# Fuente.net
KiCad netlist of a schematic drawn in EAGLE
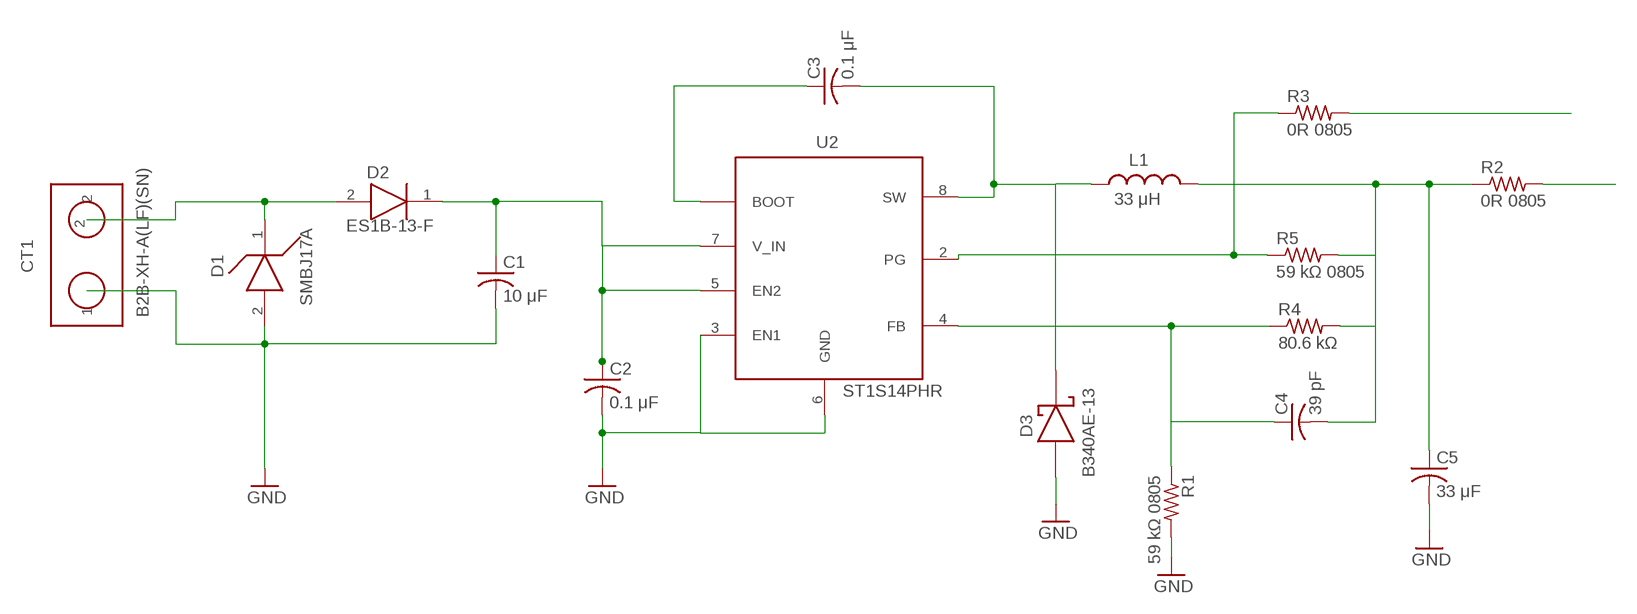
[diagram p0: schematic, sheet 1]

(export (version "E")
  (design (tool "Eeschema 10.0.6"))
  (components
    (comp (ref "C1")
      (value "10 μF")
      (footprint "eagle-import:C0805")
      (fields (field (name "PART_NO") "GRM21BR61H106KE43L"))
      (libsource (lib "eagle-import") (part "C-USC0805"))
    )
    (comp (ref "C2")
      (value "0.1 μF")
      (footprint "eagle-import:C0805")
      (fields (field (name "PART_NO") "GCM21BR72A104KA37L"))
      (libsource (lib "eagle-import") (part "C-USC0805"))
    )
    (comp (ref "C3")
      (value "0.1 μF")
      (footprint "eagle-import:C0805")
      (fields (field (name "PART_NO") "GCM21BR72A104KA37L"))
      (libsource (lib "eagle-import") (part "C-USC0805"))
    )
    (comp (ref "C4")
      (value "39 pF")
      (footprint "eagle-import:C0805")
      (fields (field (name "PART_NO") "GRM21A5C2E390JW01D"))
      (libsource (lib "eagle-import") (part "C-USC0805"))
    )
    (comp (ref "C5")
      (value "33 μF")
      (footprint "eagle-import:C0805")
      (fields (field (name "PART_NO") "GRM21BR60G336ME15L"))
      (libsource (lib "eagle-import") (part "C-USC0805"))
    )
    (comp (ref "CT1")
      (value "B2B-XH-A(LF)(SN)")
      (footprint "eagle-import:2-PIN-XH-JST")
      (libsource (lib "eagle-import") (part "B2B-XH-A(LF)(SN)"))
    )
    (comp (ref "D1")
      (value "SMBJ17A")
      (footprint "eagle-import:DO-214AA")
      (libsource (lib "eagle-import") (part "SMBJ17A"))
    )
    (comp (ref "D2")
      (value "ES1B-13-F")
      (footprint "eagle-import:DO-214AC")
      (libsource (lib "eagle-import") (part "ES1B-13-F"))
    )
    (comp (ref "D3")
      (value "B340AE-13")
      (footprint "eagle-import:DO-214AC")
      (libsource (lib "eagle-import") (part "B340AE-13-DI"))
    )
    (comp (ref "L1")
      (value "33 μH")
      (footprint "eagle-import:SMD")
      (fields (field (name "PART_NO") "LVS606045-330M-N"))
      (libsource (lib "eagle-import") (part "LVS606045-330M-N"))
    )
    (comp (ref "R1")
      (value "59 kΩ 0805")
      (footprint "eagle-import:R0805")
      (fields (field (name "PART_NO") "RC0805FR-0759KL "))
      (libsource (lib "eagle-import") (part "R-US_R0805"))
    )
    (comp (ref "R2")
      (value "0R 0805")
      (footprint "eagle-import:R0805")
      (libsource (lib "eagle-import") (part "R-US_R0805"))
    )
    (comp (ref "R3")
      (value "0R 0805")
      (footprint "eagle-import:R0805")
      (libsource (lib "eagle-import") (part "R-US_R0805"))
    )
    (comp (ref "R4")
      (value "80.6 kΩ")
      (footprint "eagle-import:R0805")
      (fields (field (name "PART_NO") "RC0805FR-0780K6L"))
      (libsource (lib "eagle-import") (part "R-US_R0805"))
    )
    (comp (ref "R5")
      (value "59 kΩ 0805")
      (footprint "eagle-import:R0805")
      (fields (field (name "PART_NO") "RC0805FR-0759KL "))
      (libsource (lib "eagle-import") (part "R-US_R0805"))
    )
    (comp (ref "U2")
      (value "ST1S14PHR")
      (footprint "eagle-import:8-SOIC")
      (libsource (lib "eagle-import") (part "ST1S14PHR"))
    )
  )
  (nets
    (net (code "1") (name "GND") (class "Default")
      (node (ref "C1") (pin "2") (pinfunction "2_2") (pintype "passive"))
      (node (ref "C2") (pin "2") (pinfunction "2_2") (pintype "passive"))
      (node (ref "C5") (pin "2") (pinfunction "2_2") (pintype "passive"))
      (node (ref "CT1") (pin "1") (pinfunction "1_1") (pintype "passive"))
      (node (ref "D1") (pin "2") (pinfunction "A_2") (pintype "passive"))
      (node (ref "D3") (pin "2") (pinfunction "ANODO_2") (pintype "passive"))
      (node (ref "R1") (pin "2") (pinfunction "2_2") (pintype "passive"))
      (node (ref "U2") (pin "3") (pinfunction "EN1_3") (pintype "passive"))
      (node (ref "U2") (pin "6") (pinfunction "GND_6") (pintype "power_in"))
    )
    (net (code "2") (name "Net-(C4-Pad2)") (class "Default")
      (node (ref "C4") (pin "2") (pinfunction "2_2") (pintype "passive"))
      (node (ref "C5") (pin "1") (pinfunction "1_1") (pintype "passive"))
      (node (ref "L1") (pin "2") (pinfunction "2_2") (pintype "passive"))
      (node (ref "R2") (pin "1") (pinfunction "1_1") (pintype "passive"))
      (node (ref "R4") (pin "2") (pinfunction "2_2") (pintype "passive"))
      (node (ref "R5") (pin "2") (pinfunction "2_2") (pintype "passive"))
    )
    (net (code "3") (name "Net-(D1-C)") (class "Default")
      (node (ref "CT1") (pin "2") (pinfunction "2_2") (pintype "passive"))
      (node (ref "D1") (pin "1") (pinfunction "C_1") (pintype "passive"))
      (node (ref "D2") (pin "2") (pinfunction "A_2") (pintype "passive"))
    )
    (net (code "4") (name "Net-(D2-C)") (class "Default")
      (node (ref "C1") (pin "1") (pinfunction "1_1") (pintype "passive"))
      (node (ref "C2") (pin "1") (pinfunction "1_1") (pintype "passive"))
      (node (ref "D2") (pin "1") (pinfunction "C_1") (pintype "passive"))
      (node (ref "U2") (pin "5") (pinfunction "EN2_5") (pintype "passive"))
      (node (ref "U2") (pin "7") (pinfunction "V_IN_7") (pintype "passive"))
    )
    (net (code "5") (name "Net-(D3-CATODO)") (class "Default")
      (node (ref "C3") (pin "2") (pinfunction "2_2") (pintype "passive"))
      (node (ref "D3") (pin "1") (pinfunction "CATODO_1") (pintype "passive"))
      (node (ref "L1") (pin "1") (pinfunction "1_1") (pintype "passive"))
      (node (ref "U2") (pin "8") (pinfunction "SW_8") (pintype "passive"))
    )
    (net (code "6") (name "Net-(U2-BOOT)") (class "Default")
      (node (ref "C3") (pin "1") (pinfunction "1_1") (pintype "passive"))
      (node (ref "U2") (pin "1") (pinfunction "BOOT_1") (pintype "passive"))
    )
    (net (code "7") (name "Net-(U2-FB)") (class "Default")
      (node (ref "C4") (pin "1") (pinfunction "1_1") (pintype "passive"))
      (node (ref "R1") (pin "1") (pinfunction "1_1") (pintype "passive"))
      (node (ref "R4") (pin "1") (pinfunction "1_1") (pintype "passive"))
      (node (ref "U2") (pin "4") (pinfunction "FB_4") (pintype "passive"))
    )
    (net (code "8") (name "Net-(U2-PG)") (class "Default")
      (node (ref "R3") (pin "1") (pinfunction "1_1") (pintype "passive"))
      (node (ref "R5") (pin "1") (pinfunction "1_1") (pintype "passive"))
      (node (ref "U2") (pin "2") (pinfunction "PG_2") (pintype "passive"))
    )
    (net (code "9") (name "unconnected-(R2-Pad2)") (class "Default")
      (node (ref "R2") (pin "2") (pinfunction "2_2") (pintype "passive"))
    )
    (net (code "10") (name "unconnected-(R3-Pad2)") (class "Default")
      (node (ref "R3") (pin "2") (pinfunction "2_2") (pintype "passive"))
    )
  )
)
